# QuadHybridV1.net
KiCad netlist of a schematic drawn in EAGLE
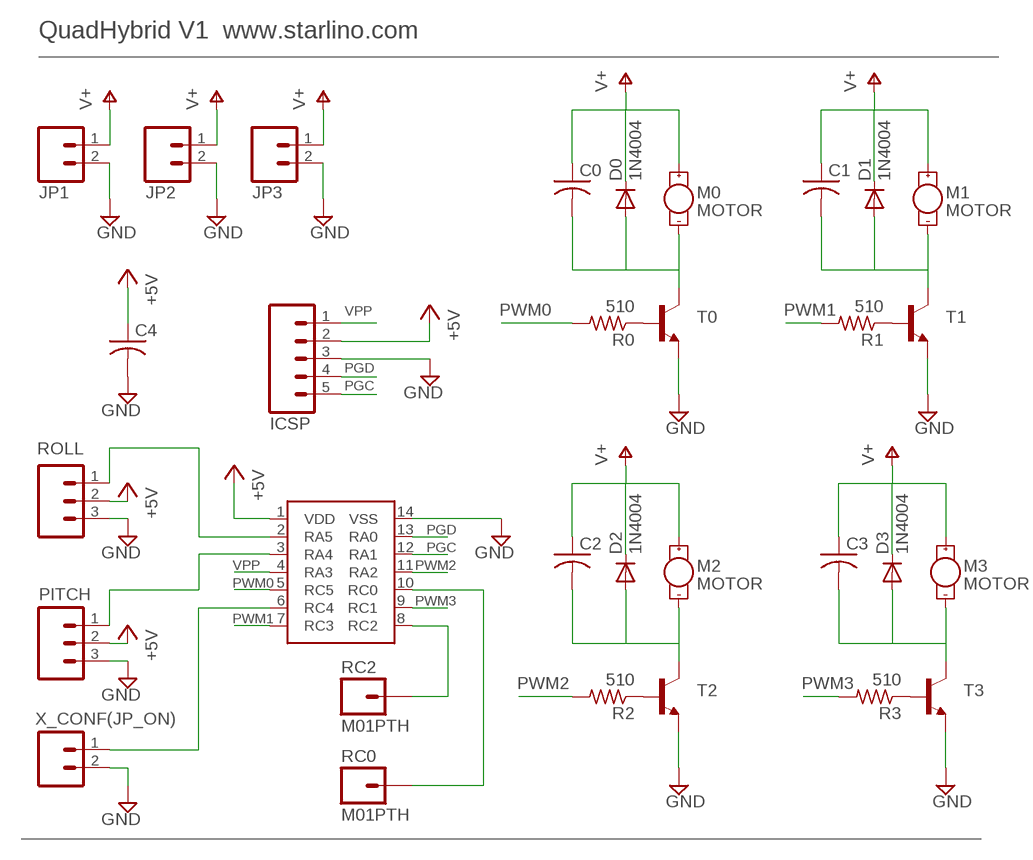
[diagram p0: schematic, sheet 1]

(export (version "E")
  (design (tool "Eeschema 10.0.6"))
  (components
    (comp (ref "C0")
      (value "C-US025-024X044")
      (footprint "eagle-import:C025-024X044")
      (libsource (lib "eagle-import") (part "C-US025-024X044"))
    )
    (comp (ref "C1")
      (value "C-US025-024X044")
      (footprint "eagle-import:C025-024X044")
      (libsource (lib "eagle-import") (part "C-US025-024X044"))
    )
    (comp (ref "C2")
      (value "C-US025-024X044")
      (footprint "eagle-import:C025-024X044")
      (libsource (lib "eagle-import") (part "C-US025-024X044"))
    )
    (comp (ref "C3")
      (value "C-US025-024X044")
      (footprint "eagle-import:C025-024X044")
      (libsource (lib "eagle-import") (part "C-US025-024X044"))
    )
    (comp (ref "C4")
      (value "C-US025-024X044")
      (footprint "eagle-import:C025-024X044")
      (libsource (lib "eagle-import") (part "C-US025-024X044"))
    )
    (comp (ref "D0")
      (value "1N4004")
      (footprint "eagle-import:DO41-10")
      (libsource (lib "eagle-import") (part "1N4004"))
    )
    (comp (ref "D1")
      (value "1N4004")
      (footprint "eagle-import:DO41-10")
      (libsource (lib "eagle-import") (part "1N4004"))
    )
    (comp (ref "D2")
      (value "1N4004")
      (footprint "eagle-import:DO41-10")
      (libsource (lib "eagle-import") (part "1N4004"))
    )
    (comp (ref "D3")
      (value "1N4004")
      (footprint "eagle-import:DO41-10")
      (libsource (lib "eagle-import") (part "1N4004"))
    )
    (comp (ref "ICSP")
      (value "M05PTH")
      (footprint "eagle-import:1X05")
      (libsource (lib "eagle-import") (part "M05PTH"))
    )
    (comp (ref "JP1")
      (value "M02PTH")
      (footprint "eagle-import:1X02")
      (libsource (lib "eagle-import") (part "M02PTH"))
    )
    (comp (ref "JP2")
      (value "M02PTH")
      (footprint "eagle-import:1X02")
      (libsource (lib "eagle-import") (part "M02PTH"))
    )
    (comp (ref "JP3")
      (value "M02PTH")
      (footprint "eagle-import:1X02")
      (libsource (lib "eagle-import") (part "M02PTH"))
    )
    (comp (ref "M0")
      (value "MOTOR")
      (footprint "eagle-import:1X02")
      (libsource (lib "eagle-import") (part "MOTOR"))
    )
    (comp (ref "M1")
      (value "MOTOR")
      (footprint "eagle-import:1X02")
      (libsource (lib "eagle-import") (part "MOTOR"))
    )
    (comp (ref "M2")
      (value "MOTOR")
      (footprint "eagle-import:1X02")
      (libsource (lib "eagle-import") (part "MOTOR"))
    )
    (comp (ref "M3")
      (value "MOTOR")
      (footprint "eagle-import:1X02")
      (libsource (lib "eagle-import") (part "MOTOR"))
    )
    (comp (ref "PIC16F1825")
      (value "PIC16F1825PDIP")
      (footprint "eagle-import:DIL14")
      (libsource (lib "eagle-import") (part "PIC16F1825PDIP"))
    )
    (comp (ref "PITCH")
      (value "M03PTH")
      (footprint "eagle-import:1X03")
      (libsource (lib "eagle-import") (part "M03PTH"))
    )
    (comp (ref "R0")
      (value "510")
      (footprint "eagle-import:0207_10")
      (libsource (lib "eagle-import") (part "R-US_0207/10"))
    )
    (comp (ref "R1")
      (value "510")
      (footprint "eagle-import:0207_10")
      (libsource (lib "eagle-import") (part "R-US_0207/10"))
    )
    (comp (ref "R2")
      (value "510")
      (footprint "eagle-import:0207_10")
      (libsource (lib "eagle-import") (part "R-US_0207/10"))
    )
    (comp (ref "R3")
      (value "510")
      (footprint "eagle-import:0207_10")
      (libsource (lib "eagle-import") (part "R-US_0207/10"))
    )
    (comp (ref "RC0")
      (value "M01PTH")
      (footprint "eagle-import:1X01")
      (libsource (lib "eagle-import") (part "M01PTH"))
    )
    (comp (ref "RC2")
      (value "M01PTH")
      (footprint "eagle-import:1X01")
      (libsource (lib "eagle-import") (part "M01PTH"))
    )
    (comp (ref "ROLL")
      (value "M03PTH")
      (footprint "eagle-import:1X03")
      (libsource (lib "eagle-import") (part "M03PTH"))
    )
    (comp (ref "T0")
      (value "-NPN-TO92-ECB")
      (footprint "eagle-import:TO92-ECB")
      (libsource (lib "eagle-import") (part "-NPN-TO92-ECB"))
    )
    (comp (ref "T1")
      (value "-NPN-TO92-ECB")
      (footprint "eagle-import:TO92-ECB")
      (libsource (lib "eagle-import") (part "-NPN-TO92-ECB"))
    )
    (comp (ref "T2")
      (value "-NPN-TO92-ECB")
      (footprint "eagle-import:TO92-ECB")
      (libsource (lib "eagle-import") (part "-NPN-TO92-ECB"))
    )
    (comp (ref "T3")
      (value "-NPN-TO92-ECB")
      (footprint "eagle-import:TO92-ECB")
      (libsource (lib "eagle-import") (part "-NPN-TO92-ECB"))
    )
    (comp (ref "X_CONF(JP_ON)")
      (value "M02PTH")
      (footprint "eagle-import:1X02")
      (libsource (lib "eagle-import") (part "M02PTH"))
    )
  )
  (nets
    (net (code "1") (name "+5V") (class "Default")
      (node (ref "C4") (pin "1") (pinfunction "1_1") (pintype "passive"))
      (node (ref "ICSP") (pin "2") (pinfunction "2_2") (pintype "passive"))
      (node (ref "PIC16F1825") (pin "1") (pinfunction "VDD_1") (pintype "power_in"))
      (node (ref "PITCH") (pin "2") (pinfunction "2_2") (pintype "passive"))
      (node (ref "ROLL") (pin "2") (pinfunction "2_2") (pintype "passive"))
    )
    (net (code "2") (name "/PGC") (class "Default")
      (node (ref "ICSP") (pin "5") (pinfunction "5_5") (pintype "passive"))
      (node (ref "PIC16F1825") (pin "12") (pinfunction "RA1_12") (pintype "bidirectional"))
    )
    (net (code "3") (name "/PGD") (class "Default")
      (node (ref "ICSP") (pin "4") (pinfunction "4_4") (pintype "passive"))
      (node (ref "PIC16F1825") (pin "13") (pinfunction "RA0_13") (pintype "bidirectional"))
    )
    (net (code "4") (name "/PWM0") (class "Default")
      (node (ref "PIC16F1825") (pin "5") (pinfunction "RC5_5") (pintype "bidirectional"))
      (node (ref "R0") (pin "2") (pinfunction "2_2") (pintype "passive"))
    )
    (net (code "5") (name "/PWM1") (class "Default")
      (node (ref "PIC16F1825") (pin "7") (pinfunction "RC3_7") (pintype "bidirectional"))
      (node (ref "R1") (pin "2") (pinfunction "2_2") (pintype "passive"))
    )
    (net (code "6") (name "/PWM2") (class "Default")
      (node (ref "PIC16F1825") (pin "11") (pinfunction "RA2_11") (pintype "bidirectional"))
      (node (ref "R2") (pin "2") (pinfunction "2_2") (pintype "passive"))
    )
    (net (code "7") (name "/PWM3") (class "Default")
      (node (ref "PIC16F1825") (pin "9") (pinfunction "RC1_9") (pintype "bidirectional"))
      (node (ref "R3") (pin "2") (pinfunction "2_2") (pintype "passive"))
    )
    (net (code "8") (name "/VPP") (class "Default")
      (node (ref "ICSP") (pin "1") (pinfunction "1_1") (pintype "passive"))
      (node (ref "PIC16F1825") (pin "4") (pinfunction "RA3_4") (pintype "input"))
    )
    (net (code "9") (name "GND") (class "Default")
      (node (ref "C4") (pin "2") (pinfunction "2_2") (pintype "passive"))
      (node (ref "ICSP") (pin "3") (pinfunction "3_3") (pintype "passive"))
      (node (ref "JP1") (pin "2") (pinfunction "2_2") (pintype "passive"))
      (node (ref "JP2") (pin "2") (pinfunction "2_2") (pintype "passive"))
      (node (ref "JP3") (pin "2") (pinfunction "2_2") (pintype "passive"))
      (node (ref "PIC16F1825") (pin "14") (pinfunction "VSS_14") (pintype "power_in"))
      (node (ref "PITCH") (pin "3") (pinfunction "3_3") (pintype "passive"))
      (node (ref "ROLL") (pin "3") (pinfunction "3_3") (pintype "passive"))
      (node (ref "T0") (pin "E") (pinfunction "E_E") (pintype "passive"))
      (node (ref "T1") (pin "E") (pinfunction "E_E") (pintype "passive"))
      (node (ref "T2") (pin "E") (pinfunction "E_E") (pintype "passive"))
      (node (ref "T3") (pin "E") (pinfunction "E_E") (pintype "passive"))
      (node (ref "X_CONF(JP_ON)") (pin "2") (pinfunction "2_2") (pintype "passive"))
    )
    (net (code "10") (name "Net-(M0--)") (class "Default")
      (node (ref "C0") (pin "2") (pinfunction "2_2") (pintype "passive"))
      (node (ref "D0") (pin "A") (pinfunction "A_A") (pintype "passive"))
      (node (ref "M0") (pin "2") (pinfunction "-_2") (pintype "bidirectional"))
      (node (ref "T0") (pin "C") (pinfunction "C_C") (pintype "passive"))
    )
    (net (code "11") (name "Net-(M1--)") (class "Default")
      (node (ref "C1") (pin "2") (pinfunction "2_2") (pintype "passive"))
      (node (ref "D1") (pin "A") (pinfunction "A_A") (pintype "passive"))
      (node (ref "M1") (pin "2") (pinfunction "-_2") (pintype "bidirectional"))
      (node (ref "T1") (pin "C") (pinfunction "C_C") (pintype "passive"))
    )
    (net (code "12") (name "Net-(M2--)") (class "Default")
      (node (ref "C2") (pin "2") (pinfunction "2_2") (pintype "passive"))
      (node (ref "D2") (pin "A") (pinfunction "A_A") (pintype "passive"))
      (node (ref "M2") (pin "2") (pinfunction "-_2") (pintype "bidirectional"))
      (node (ref "T2") (pin "C") (pinfunction "C_C") (pintype "passive"))
    )
    (net (code "13") (name "Net-(M3--)") (class "Default")
      (node (ref "C3") (pin "2") (pinfunction "2_2") (pintype "passive"))
      (node (ref "D3") (pin "A") (pinfunction "A_A") (pintype "passive"))
      (node (ref "M3") (pin "2") (pinfunction "-_2") (pintype "bidirectional"))
      (node (ref "T3") (pin "C") (pinfunction "C_C") (pintype "passive"))
    )
    (net (code "14") (name "Net-(PIC16F1825-RA4)") (class "Default")
      (node (ref "PIC16F1825") (pin "3") (pinfunction "RA4_3") (pintype "bidirectional"))
      (node (ref "PITCH") (pin "1") (pinfunction "1_1") (pintype "passive"))
    )
    (net (code "15") (name "Net-(PIC16F1825-RA5)") (class "Default")
      (node (ref "PIC16F1825") (pin "2") (pinfunction "RA5_2") (pintype "bidirectional"))
      (node (ref "ROLL") (pin "1") (pinfunction "1_1") (pintype "passive"))
    )
    (net (code "16") (name "Net-(PIC16F1825-RC0)") (class "Default")
      (node (ref "PIC16F1825") (pin "10") (pinfunction "RC0_10") (pintype "bidirectional"))
      (node (ref "RC0") (pin "1") (pinfunction "1_1") (pintype "passive"))
    )
    (net (code "17") (name "Net-(PIC16F1825-RC2)") (class "Default")
      (node (ref "PIC16F1825") (pin "8") (pinfunction "RC2_8") (pintype "bidirectional"))
      (node (ref "RC2") (pin "1") (pinfunction "1_1") (pintype "passive"))
    )
    (net (code "18") (name "Net-(PIC16F1825-RC4)") (class "Default")
      (node (ref "PIC16F1825") (pin "6") (pinfunction "RC4_6") (pintype "bidirectional"))
      (node (ref "X_CONF(JP_ON)") (pin "1") (pinfunction "1_1") (pintype "passive"))
    )
    (net (code "19") (name "Net-(R0-Pad1)") (class "Default")
      (node (ref "R0") (pin "1") (pinfunction "1_1") (pintype "passive"))
      (node (ref "T0") (pin "B") (pinfunction "B_B") (pintype "passive"))
    )
    (net (code "20") (name "Net-(R1-Pad1)") (class "Default")
      (node (ref "R1") (pin "1") (pinfunction "1_1") (pintype "passive"))
      (node (ref "T1") (pin "B") (pinfunction "B_B") (pintype "passive"))
    )
    (net (code "21") (name "Net-(R2-Pad1)") (class "Default")
      (node (ref "R2") (pin "1") (pinfunction "1_1") (pintype "passive"))
      (node (ref "T2") (pin "B") (pinfunction "B_B") (pintype "passive"))
    )
    (net (code "22") (name "Net-(R3-Pad1)") (class "Default")
      (node (ref "R3") (pin "1") (pinfunction "1_1") (pintype "passive"))
      (node (ref "T3") (pin "B") (pinfunction "B_B") (pintype "passive"))
    )
    (net (code "23") (name "V+") (class "Default")
      (node (ref "C0") (pin "1") (pinfunction "1_1") (pintype "passive"))
      (node (ref "C1") (pin "1") (pinfunction "1_1") (pintype "passive"))
      (node (ref "C2") (pin "1") (pinfunction "1_1") (pintype "passive"))
      (node (ref "C3") (pin "1") (pinfunction "1_1") (pintype "passive"))
      (node (ref "D0") (pin "C") (pinfunction "C_C") (pintype "passive"))
      (node (ref "D1") (pin "C") (pinfunction "C_C") (pintype "passive"))
      (node (ref "D2") (pin "C") (pinfunction "C_C") (pintype "passive"))
      (node (ref "D3") (pin "C") (pinfunction "C_C") (pintype "passive"))
      (node (ref "JP1") (pin "1") (pinfunction "1_1") (pintype "passive"))
      (node (ref "JP2") (pin "1") (pinfunction "1_1") (pintype "passive"))
      (node (ref "JP3") (pin "1") (pinfunction "1_1") (pintype "passive"))
      (node (ref "M0") (pin "1") (pinfunction "+_1") (pintype "bidirectional"))
      (node (ref "M1") (pin "1") (pinfunction "+_1") (pintype "bidirectional"))
      (node (ref "M2") (pin "1") (pinfunction "+_1") (pintype "bidirectional"))
      (node (ref "M3") (pin "1") (pinfunction "+_1") (pintype "bidirectional"))
    )
  )
)
